# switchboard_schematic.net
KiCad netlist of a schematic drawn in Altium Designer
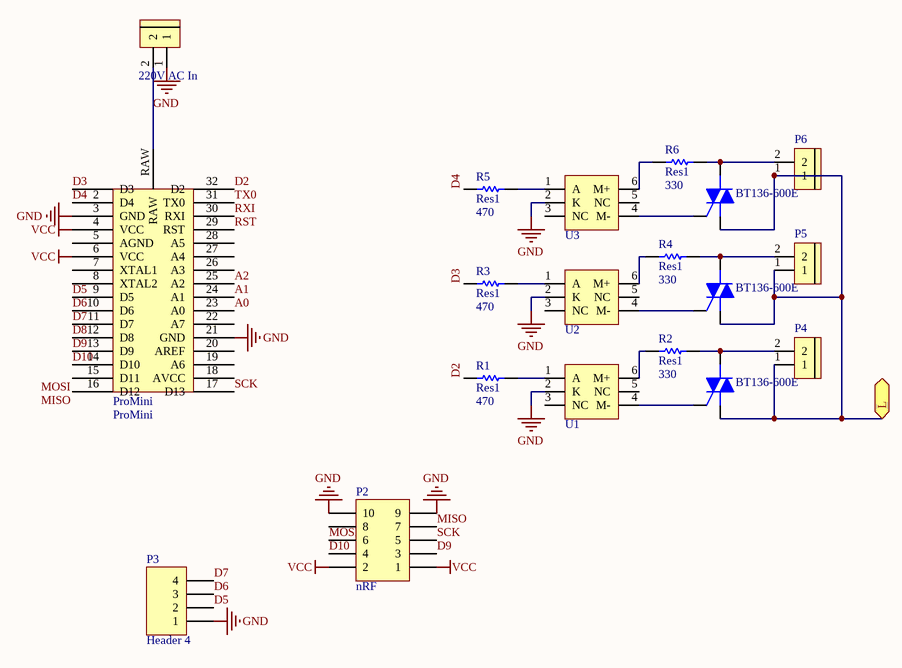
[diagram p0: switchboard_schematic.SchDoc]

(export (version "E")
  (design (tool "Eeschema 10.0.6"))
  (components
    (comp (ref "P1")
      (value "220V AC In")
      (footprint "BIG_Header 2")
      (libsource (lib "") (part "BIG_Header 2_1"))
    )
    (comp (ref "P2")
      (value "nRF")
      (footprint "HDR2X5")
      (description "Header, 5-Pin, Dual row")
      (fields (field (name "PUBLISHER") "Altium Limited"))
      (libsource (lib "Miscellaneous Connectors") (part "Header 5X2"))
    )
    (comp (ref "P3")
      (value "Header 4")
      (footprint "HDR1X4")
      (description "Header, 4-Pin")
      (fields (field (name "PUBLISHER") "Altium Limited"))
      (libsource (lib "Miscellaneous Connectors") (part "Header 4"))
    )
    (comp (ref "P4")
      (value "BIG_Header 2")
      (footprint "BIG_Header 2")
      (libsource (lib "NBBLib 14-03-2012") (part "BIG_Header 2"))
    )
    (comp (ref "P5")
      (value "BIG_Header 2")
      (footprint "BIG_Header 2")
      (libsource (lib "NBBLib 14-03-2012") (part "BIG_Header 2"))
    )
    (comp (ref "P6")
      (value "BIG_Header 2")
      (footprint "BIG_Header 2")
      (libsource (lib "NBBLib 14-03-2012") (part "BIG_Header 2"))
    )
    (comp (ref "ProMini")
      (value "ProMini")
      (footprint "Arduino Pro Mini")
      (libsource (lib "ArduinoLib") (part "Pro Mini"))
    )
    (comp (ref "Q1")
      (value "BT136-600E")
      (footprint "BTA6-600")
      (description "Silicon Bidirectional Triode Thyristor")
      (fields (field (name "PUBLISHER") "Altium Limited"))
      (libsource (lib "NBBLib 14-03-2012") (part "BTA12-600"))
    )
    (comp (ref "Q2")
      (value "BT136-600E")
      (footprint "BTA6-600")
      (description "Silicon Bidirectional Triode Thyristor")
      (fields (field (name "PUBLISHER") "Altium Limited"))
      (libsource (lib "NBBLib 14-03-2012") (part "BTA12-600"))
    )
    (comp (ref "Q3")
      (value "BT136-600E")
      (footprint "BTA6-600")
      (description "Silicon Bidirectional Triode Thyristor")
      (fields (field (name "PUBLISHER") "Altium Limited"))
      (libsource (lib "NBBLib 14-03-2012") (part "BTA12-600"))
    )
    (comp (ref "R1")
      (value "Res1")
      (footprint "AXIAL-0.3")
      (description "Resistor")
      (fields (field (name "ALTIUM_VALUE") "470") (field (name "PUBLISHER") "Altium Limited"))
      (libsource (lib "Miscellaneous Devices") (part "Res1"))
    )
    (comp (ref "R2")
      (value "Res1")
      (footprint "AXIAL-0.3")
      (description "Resistor")
      (fields (field (name "ALTIUM_VALUE") "330") (field (name "PUBLISHER") "Altium Limited"))
      (libsource (lib "Miscellaneous Devices") (part "Res1"))
    )
    (comp (ref "R3")
      (value "Res1")
      (footprint "AXIAL-0.3")
      (description "Resistor")
      (fields (field (name "ALTIUM_VALUE") "470") (field (name "PUBLISHER") "Altium Limited"))
      (libsource (lib "Miscellaneous Devices") (part "Res1"))
    )
    (comp (ref "R4")
      (value "Res1")
      (footprint "AXIAL-0.3")
      (description "Resistor")
      (fields (field (name "ALTIUM_VALUE") "330") (field (name "PUBLISHER") "Altium Limited"))
      (libsource (lib "Miscellaneous Devices") (part "Res1"))
    )
    (comp (ref "R5")
      (value "Res1")
      (footprint "AXIAL-0.3")
      (description "Resistor")
      (fields (field (name "ALTIUM_VALUE") "470") (field (name "PUBLISHER") "Altium Limited"))
      (libsource (lib "Miscellaneous Devices") (part "Res1"))
    )
    (comp (ref "R6")
      (value "Res1")
      (footprint "AXIAL-0.3")
      (description "Resistor")
      (fields (field (name "ALTIUM_VALUE") "330") (field (name "PUBLISHER") "Altium Limited"))
      (libsource (lib "Miscellaneous Devices") (part "Res1"))
    )
    (comp (ref "U1")
      (value "MOC3021M")
      (footprint "MOC30XX")
      (libsource (lib "NBBLib 14-03-2012") (part "MOC3021M"))
    )
    (comp (ref "U2")
      (value "MOC3021M")
      (footprint "MOC30XX")
      (libsource (lib "NBBLib 14-03-2012") (part "MOC3021M"))
    )
    (comp (ref "U3")
      (value "MOC3021M")
      (footprint "MOC30XX")
      (libsource (lib "NBBLib 14-03-2012") (part "MOC3021M"))
    )
  )
  (nets
    (net (code "1") (name "/A0") (class "Default")
      (node (ref "ProMini") (pin "23") (pinfunction "A0_23") (pintype "passive"))
    )
    (net (code "2") (name "/A1") (class "Default")
      (node (ref "ProMini") (pin "24") (pinfunction "A1_24") (pintype "passive"))
    )
    (net (code "3") (name "/A2") (class "Default")
      (node (ref "ProMini") (pin "25") (pinfunction "A2_25") (pintype "passive"))
    )
    (net (code "4") (name "/D2") (class "Default")
      (node (ref "ProMini") (pin "32") (pinfunction "D2_32") (pintype "passive"))
      (node (ref "R1") (pin "1") (pinfunction "1_1") (pintype "passive"))
    )
    (net (code "5") (name "/D3") (class "Default")
      (node (ref "ProMini") (pin "1") (pinfunction "D3_1") (pintype "passive"))
      (node (ref "R3") (pin "1") (pinfunction "1_1") (pintype "passive"))
    )
    (net (code "6") (name "/D4") (class "Default")
      (node (ref "ProMini") (pin "2") (pinfunction "D4_2") (pintype "passive"))
      (node (ref "R5") (pin "1") (pinfunction "1_1") (pintype "passive"))
    )
    (net (code "7") (name "/D5") (class "Default")
      (node (ref "P3") (pin "2") (pinfunction "2_2") (pintype "passive"))
      (node (ref "ProMini") (pin "9") (pinfunction "D5_9") (pintype "passive"))
    )
    (net (code "8") (name "/D6") (class "Default")
      (node (ref "P3") (pin "3") (pinfunction "3_3") (pintype "passive"))
      (node (ref "ProMini") (pin "10") (pinfunction "D6_10") (pintype "passive"))
    )
    (net (code "9") (name "/D7") (class "Default")
      (node (ref "P3") (pin "4") (pinfunction "4_4") (pintype "passive"))
      (node (ref "ProMini") (pin "11") (pinfunction "D7_11") (pintype "passive"))
    )
    (net (code "10") (name "/D8") (class "Default")
      (node (ref "ProMini") (pin "12") (pinfunction "D8_12") (pintype "passive"))
    )
    (net (code "11") (name "/D9") (class "Default")
      (node (ref "P2") (pin "3") (pinfunction "3_3") (pintype "passive"))
      (node (ref "ProMini") (pin "13") (pinfunction "D9_13") (pintype "passive"))
    )
    (net (code "12") (name "/D10") (class "Default")
      (node (ref "P2") (pin "4") (pinfunction "4_4") (pintype "passive"))
      (node (ref "ProMini") (pin "14") (pinfunction "D10_14") (pintype "passive"))
    )
    (net (code "13") (name "/L") (class "Default")
      (node (ref "P4") (pin "1") (pinfunction "1_1") (pintype "passive"))
      (node (ref "P5") (pin "1") (pinfunction "1_1") (pintype "passive"))
      (node (ref "P6") (pin "1") (pinfunction "1_1") (pintype "passive"))
      (node (ref "Q1") (pin "1") (pinfunction "M1_1") (pintype "passive"))
      (node (ref "Q2") (pin "1") (pinfunction "M1_1") (pintype "passive"))
      (node (ref "Q3") (pin "1") (pinfunction "M1_1") (pintype "passive"))
    )
    (net (code "14") (name "/MISO") (class "Default")
      (node (ref "P2") (pin "7") (pinfunction "7_7") (pintype "passive"))
      (node (ref "ProMini") (pin "16") (pinfunction "D12_16") (pintype "passive"))
    )
    (net (code "15") (name "/MOSI") (class "Default")
      (node (ref "P2") (pin "6") (pinfunction "6_6") (pintype "passive"))
      (node (ref "ProMini") (pin "15") (pinfunction "D11_15") (pintype "passive"))
    )
    (net (code "16") (name "/RST") (class "Default")
      (node (ref "ProMini") (pin "29") (pinfunction "RST_29") (pintype "passive"))
    )
    (net (code "17") (name "/RXI") (class "Default")
      (node (ref "ProMini") (pin "30") (pinfunction "RXI_30") (pintype "passive"))
    )
    (net (code "18") (name "/SCK") (class "Default")
      (node (ref "P2") (pin "5") (pinfunction "5_5") (pintype "passive"))
      (node (ref "ProMini") (pin "17") (pinfunction "D13_17") (pintype "passive"))
    )
    (net (code "19") (name "/TX0") (class "Default")
      (node (ref "ProMini") (pin "31") (pinfunction "TX0_31") (pintype "passive"))
    )
    (net (code "20") (name "GND") (class "Default")
      (node (ref "P1") (pin "1") (pinfunction "1_1") (pintype "passive"))
      (node (ref "P2") (pin "10") (pinfunction "10_10") (pintype "passive"))
      (node (ref "P2") (pin "9") (pinfunction "9_9") (pintype "passive"))
      (node (ref "P3") (pin "1") (pinfunction "1_1") (pintype "passive"))
      (node (ref "ProMini") (pin "21") (pinfunction "GND_21") (pintype "passive"))
      (node (ref "ProMini") (pin "3") (pinfunction "GND_3") (pintype "passive"))
      (node (ref "U1") (pin "2") (pinfunction "K_2") (pintype "passive"))
      (node (ref "U2") (pin "2") (pinfunction "K_2") (pintype "passive"))
      (node (ref "U3") (pin "2") (pinfunction "K_2") (pintype "passive"))
    )
    (net (code "21") (name "Net-(P1-Pad2)") (class "Default")
      (node (ref "P1") (pin "2") (pinfunction "2_2") (pintype "passive"))
      (node (ref "ProMini") (pin "RAW") (pinfunction "RAW_RAW") (pintype "passive"))
    )
    (net (code "22") (name "Net-(Q1-G)") (class "Default")
      (node (ref "Q1") (pin "3") (pinfunction "G_3") (pintype "passive"))
      (node (ref "U1") (pin "4") (pinfunction "M-_4") (pintype "passive"))
    )
    (net (code "23") (name "Net-(Q1-M2)") (class "Default")
      (node (ref "P4") (pin "2") (pinfunction "2_2") (pintype "passive"))
      (node (ref "Q1") (pin "2") (pinfunction "M2_2") (pintype "passive"))
      (node (ref "R2") (pin "2") (pinfunction "2_2") (pintype "passive"))
    )
    (net (code "24") (name "Net-(Q2-G)") (class "Default")
      (node (ref "Q2") (pin "3") (pinfunction "G_3") (pintype "passive"))
      (node (ref "U2") (pin "4") (pinfunction "M-_4") (pintype "passive"))
    )
    (net (code "25") (name "Net-(Q2-M2)") (class "Default")
      (node (ref "P5") (pin "2") (pinfunction "2_2") (pintype "passive"))
      (node (ref "Q2") (pin "2") (pinfunction "M2_2") (pintype "passive"))
      (node (ref "R4") (pin "2") (pinfunction "2_2") (pintype "passive"))
    )
    (net (code "26") (name "Net-(Q3-G)") (class "Default")
      (node (ref "Q3") (pin "3") (pinfunction "G_3") (pintype "passive"))
      (node (ref "U3") (pin "4") (pinfunction "M-_4") (pintype "passive"))
    )
    (net (code "27") (name "Net-(Q3-M2)") (class "Default")
      (node (ref "P6") (pin "2") (pinfunction "2_2") (pintype "passive"))
      (node (ref "Q3") (pin "2") (pinfunction "M2_2") (pintype "passive"))
      (node (ref "R6") (pin "2") (pinfunction "2_2") (pintype "passive"))
    )
    (net (code "28") (name "Net-(U1-A)") (class "Default")
      (node (ref "R1") (pin "2") (pinfunction "2_2") (pintype "passive"))
      (node (ref "U1") (pin "1") (pinfunction "A_1") (pintype "passive"))
    )
    (net (code "29") (name "Net-(U1-M+)") (class "Default")
      (node (ref "R2") (pin "1") (pinfunction "1_1") (pintype "passive"))
      (node (ref "U1") (pin "6") (pinfunction "M+_6") (pintype "passive"))
    )
    (net (code "30") (name "Net-(U2-A)") (class "Default")
      (node (ref "R3") (pin "2") (pinfunction "2_2") (pintype "passive"))
      (node (ref "U2") (pin "1") (pinfunction "A_1") (pintype "passive"))
    )
    (net (code "31") (name "Net-(U2-M+)") (class "Default")
      (node (ref "R4") (pin "1") (pinfunction "1_1") (pintype "passive"))
      (node (ref "U2") (pin "6") (pinfunction "M+_6") (pintype "passive"))
    )
    (net (code "32") (name "Net-(U3-A)") (class "Default")
      (node (ref "R5") (pin "2") (pinfunction "2_2") (pintype "passive"))
      (node (ref "U3") (pin "1") (pinfunction "A_1") (pintype "passive"))
    )
    (net (code "33") (name "Net-(U3-M+)") (class "Default")
      (node (ref "R6") (pin "1") (pinfunction "1_1") (pintype "passive"))
      (node (ref "U3") (pin "6") (pinfunction "M+_6") (pintype "passive"))
    )
    (net (code "34") (name "VCC") (class "Default")
      (node (ref "P2") (pin "1") (pinfunction "1_1") (pintype "passive"))
      (node (ref "P2") (pin "2") (pinfunction "2_2") (pintype "passive"))
      (node (ref "ProMini") (pin "4") (pinfunction "VCC_4") (pintype "passive"))
      (node (ref "ProMini") (pin "6") (pinfunction "VCC_6") (pintype "passive"))
    )
    (net (code "35") (name "unconnected-(P2-Pad8)") (class "Default")
      (node (ref "P2") (pin "8") (pinfunction "8_8") (pintype "passive"))
    )
    (net (code "36") (name "unconnected-(ProMini-A3-Pad26)") (class "Default")
      (node (ref "ProMini") (pin "26") (pinfunction "A3_26") (pintype "passive"))
    )
    (net (code "37") (name "unconnected-(ProMini-A4-Pad27)") (class "Default")
      (node (ref "ProMini") (pin "27") (pinfunction "A4_27") (pintype "passive"))
    )
    (net (code "38") (name "unconnected-(ProMini-A5-Pad28)") (class "Default")
      (node (ref "ProMini") (pin "28") (pinfunction "A5_28") (pintype "passive"))
    )
    (net (code "39") (name "unconnected-(ProMini-A6-Pad19)") (class "Default")
      (node (ref "ProMini") (pin "19") (pinfunction "A6_19") (pintype "passive"))
    )
    (net (code "40") (name "unconnected-(ProMini-A7-Pad22)") (class "Default")
      (node (ref "ProMini") (pin "22") (pinfunction "A7_22") (pintype "passive"))
    )
    (net (code "41") (name "unconnected-(ProMini-AGND-Pad5)") (class "Default")
      (node (ref "ProMini") (pin "5") (pinfunction "AGND_5") (pintype "passive"))
    )
    (net (code "42") (name "unconnected-(ProMini-AREF-Pad20)") (class "Default")
      (node (ref "ProMini") (pin "20") (pinfunction "AREF_20") (pintype "passive"))
    )
    (net (code "43") (name "unconnected-(ProMini-AVCC-Pad18)") (class "Default")
      (node (ref "ProMini") (pin "18") (pinfunction "AVCC_18") (pintype "passive"))
    )
    (net (code "44") (name "unconnected-(ProMini-XTAL1-Pad7)") (class "Default")
      (node (ref "ProMini") (pin "7") (pinfunction "XTAL1_7") (pintype "passive"))
    )
    (net (code "45") (name "unconnected-(ProMini-XTAL2-Pad8)") (class "Default")
      (node (ref "ProMini") (pin "8") (pinfunction "XTAL2_8") (pintype "passive"))
    )
    (net (code "46") (name "unconnected-(U1-NC-Pad3)") (class "Default")
      (node (ref "U1") (pin "3") (pinfunction "NC_3") (pintype "passive"))
    )
    (net (code "47") (name "unconnected-(U1-NC-Pad5)") (class "Default")
      (node (ref "U1") (pin "5") (pinfunction "NC_5") (pintype "passive"))
    )
    (net (code "48") (name "unconnected-(U2-NC-Pad3)") (class "Default")
      (node (ref "U2") (pin "3") (pinfunction "NC_3") (pintype "passive"))
    )
    (net (code "49") (name "unconnected-(U2-NC-Pad5)") (class "Default")
      (node (ref "U2") (pin "5") (pinfunction "NC_5") (pintype "passive"))
    )
    (net (code "50") (name "unconnected-(U3-NC-Pad3)") (class "Default")
      (node (ref "U3") (pin "3") (pinfunction "NC_3") (pintype "passive"))
    )
    (net (code "51") (name "unconnected-(U3-NC-Pad5)") (class "Default")
      (node (ref "U3") (pin "5") (pinfunction "NC_5") (pintype "passive"))
    )
  )
)
